# I3C.net
KiCad netlist of a schematic drawn in Altium Designer
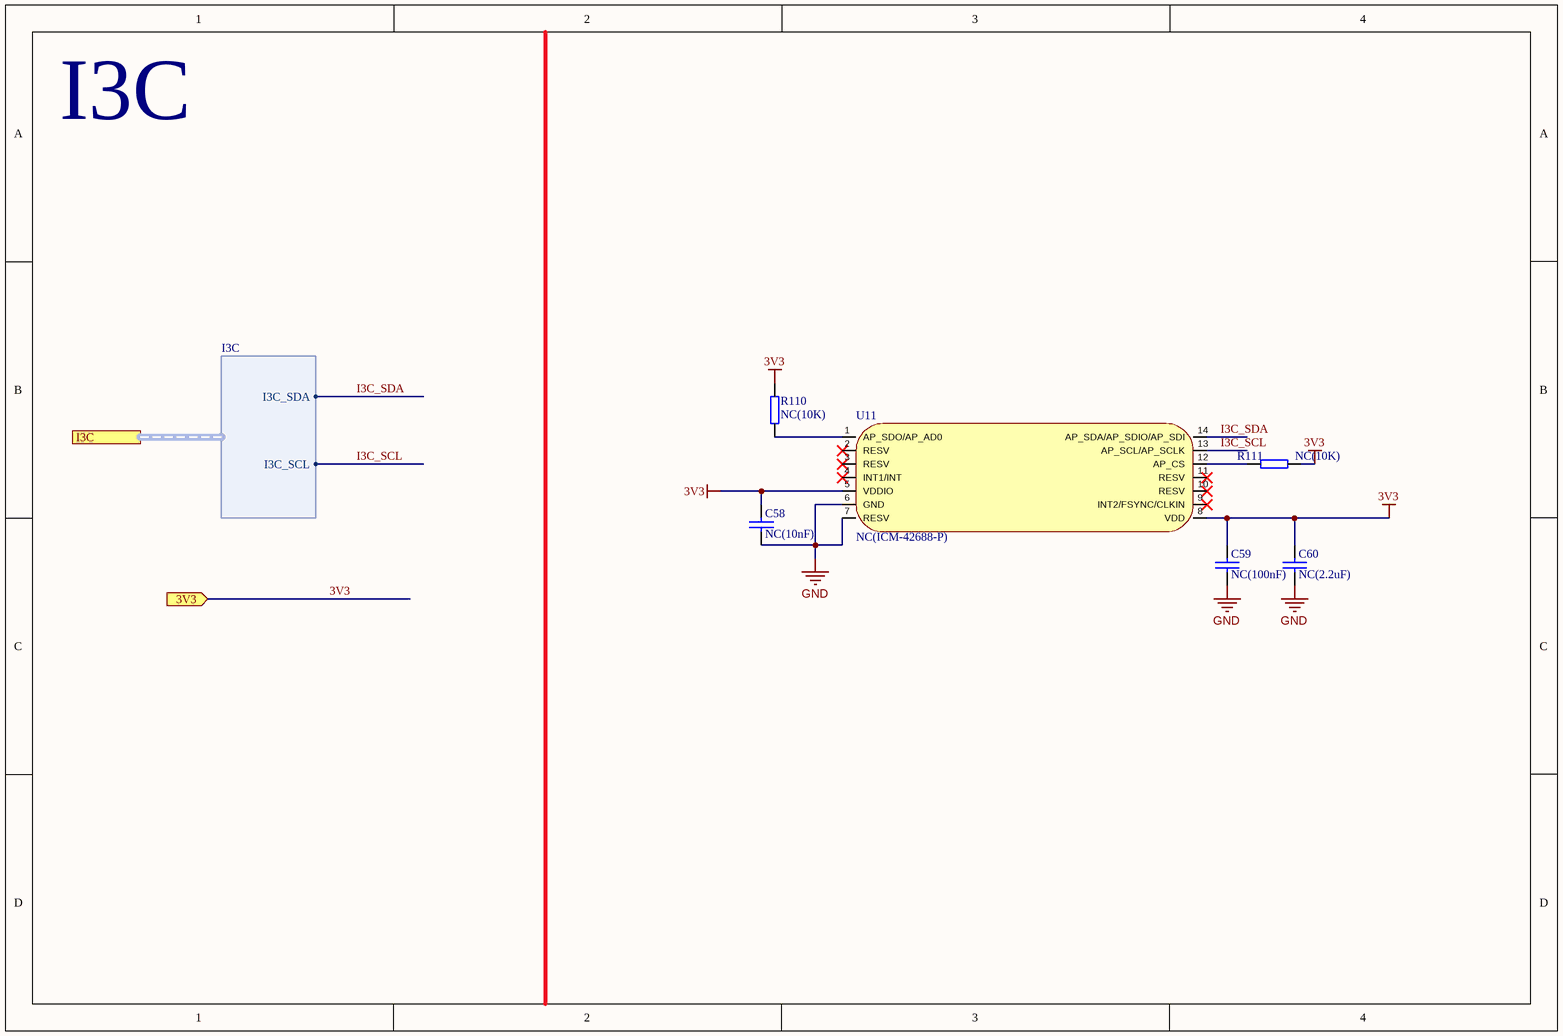
[diagram p0: I3C.SchDoc]

(export (version "E")
  (design (tool "Eeschema 10.0.6"))
  (components
    (comp (ref "C58")
      (value "NC(10nF)")
      (footprint "0402_C")
      (description "Capacitor")
      (libsource (lib "*") (part "CAP"))
    )
    (comp (ref "C59")
      (value "NC(100nF)")
      (footprint "0402_C")
      (description "Capacitor")
      (libsource (lib "*") (part "CAP"))
    )
    (comp (ref "C60")
      (value "NC(2.2uF)")
      (footprint "0402_C")
      (description "Capacitor")
      (libsource (lib "*") (part "CAP"))
    )
    (comp (ref "R110") (value "NC(10K)") (footprint "0402") (libsource (lib "*") (part "RES")))
    (comp (ref "R111") (value "NC(10K)") (footprint "0402") (libsource (lib "*") (part "RES")))
    (comp (ref "U11")
      (value "NC(ICM-42688-P)")
      (footprint "LGA-14_L3.0-W2.5-P0.50-TL")
      (libsource (lib "wch_sch_others") (part "ICM-42688-P"))
    )
  )
  (nets
    (net (code "2") (name "/I3C_SCL") (class "Default")
      (node (ref "U11") (pin "13") (pinfunction "AP_SCL/AP_SCLK_13") (pintype "passive"))
    )
    (net (code "3") (name "/I3C_SDA") (class "Default")
      (node (ref "U11") (pin "14") (pinfunction "AP_SDA/AP_SDIO/AP_SDI_14") (pintype "passive"))
    )
    (net (code "5") (name "3V3") (class "Default")
      (node (ref "C58") (pin "2") (pinfunction "2_2") (pintype "passive"))
      (node (ref "C59") (pin "2") (pinfunction "2_2") (pintype "passive"))
      (node (ref "C60") (pin "2") (pinfunction "2_2") (pintype "passive"))
      (node (ref "R110") (pin "1") (pintype "passive"))
      (node (ref "R111") (pin "1") (pintype "passive"))
      (node (ref "U11") (pin "5") (pinfunction "VDDIO_5") (pintype "passive"))
      (node (ref "U11") (pin "8") (pinfunction "VDD_8") (pintype "passive"))
    )
    (net (code "6") (name "GND") (class "Default")
      (node (ref "C58") (pin "1") (pinfunction "1_1") (pintype "passive"))
      (node (ref "C59") (pin "1") (pinfunction "1_1") (pintype "passive"))
      (node (ref "C60") (pin "1") (pinfunction "1_1") (pintype "passive"))
      (node (ref "U11") (pin "6") (pinfunction "GND_6") (pintype "passive"))
      (node (ref "U11") (pin "7") (pinfunction "RESV_7") (pintype "passive"))
    )
    (net (code "7") (name "Net-(U11-AP_CS)") (class "Default")
      (node (ref "R111") (pin "2") (pintype "passive"))
      (node (ref "U11") (pin "12") (pinfunction "AP_CS_12") (pintype "passive"))
    )
    (net (code "8") (name "Net-(U11-AP_SDO{slash}AP_AD0)") (class "Default")
      (node (ref "R110") (pin "2") (pintype "passive"))
      (node (ref "U11") (pin "1") (pinfunction "AP_SDO/AP_AD0_1") (pintype "passive"))
    )
    (net (code "9") (name "unconnected-(U11-INT1{slash}INT-Pad4)") (class "Default")
      (node (ref "U11") (pin "4") (pinfunction "INT1/INT_4") (pintype "passive+no_connect"))
    )
    (net (code "10") (name "unconnected-(U11-INT2{slash}FSYNC{slash}CLKIN-Pad9)") (class "Default")
      (node (ref "U11") (pin "9") (pinfunction "INT2/FSYNC/CLKIN_9") (pintype "passive+no_connect"))
    )
    (net (code "11") (name "unconnected-(U11-RESV-Pad2)") (class "Default")
      (node (ref "U11") (pin "2") (pinfunction "RESV_2") (pintype "passive+no_connect"))
    )
    (net (code "12") (name "unconnected-(U11-RESV-Pad3)") (class "Default")
      (node (ref "U11") (pin "3") (pinfunction "RESV_3") (pintype "passive+no_connect"))
    )
    (net (code "13") (name "unconnected-(U11-RESV-Pad10)") (class "Default")
      (node (ref "U11") (pin "10") (pinfunction "RESV_10") (pintype "passive+no_connect"))
    )
    (net (code "14") (name "unconnected-(U11-RESV-Pad11)") (class "Default")
      (node (ref "U11") (pin "11") (pinfunction "RESV_11") (pintype "passive+no_connect"))
    )
  )
)
